# Level_Shift_Breakout.net
KiCad netlist of a schematic drawn in EAGLE
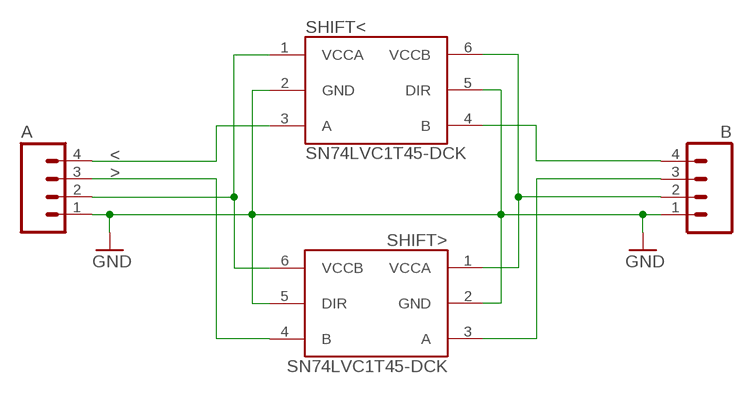
[diagram p0: schematic, sheet 1]

(export (version "E")
  (design (tool "Eeschema 10.0.6"))
  (components
    (comp (ref "A")
      (value "M04PTH")
      (footprint "eagle-import:1X04")
      (libsource (lib "eagle-import") (part "M04PTH"))
    )
    (comp (ref "B")
      (value "M04PTH")
      (footprint "eagle-import:1X04")
      (libsource (lib "eagle-import") (part "M04PTH"))
    )
    (comp (ref "SHIFT<")
      (value "SN74LVC1T45-DCK")
      (footprint "eagle-import:SC70")
      (libsource (lib "eagle-import") (part "SN74LVC1T45-DCK"))
    )
    (comp (ref "SHIFT>")
      (value "SN74LVC1T45-DCK")
      (footprint "eagle-import:SC70")
      (libsource (lib "eagle-import") (part "SN74LVC1T45-DCK"))
    )
  )
  (nets
    (net (code "1") (name "/<") (class "Default")
      (node (ref "A") (pin "4") (pinfunction "4_4") (pintype "passive"))
      (node (ref "SHIFT<") (pin "3") (pinfunction "A_3") (pintype "bidirectional"))
    )
    (net (code "2") (name "/>") (class "Default")
      (node (ref "A") (pin "3") (pinfunction "3_3") (pintype "passive"))
      (node (ref "SHIFT>") (pin "4") (pinfunction "B_4") (pintype "bidirectional"))
    )
    (net (code "3") (name "GND") (class "Default")
      (node (ref "A") (pin "1") (pinfunction "1_1") (pintype "passive"))
      (node (ref "B") (pin "1") (pinfunction "1_1") (pintype "passive"))
      (node (ref "SHIFT<") (pin "2") (pinfunction "GND_2") (pintype "bidirectional"))
      (node (ref "SHIFT<") (pin "5") (pinfunction "DIR_5") (pintype "bidirectional"))
      (node (ref "SHIFT>") (pin "2") (pinfunction "GND_2") (pintype "bidirectional"))
      (node (ref "SHIFT>") (pin "5") (pinfunction "DIR_5") (pintype "bidirectional"))
    )
    (net (code "4") (name "Net-(SHIFT<-B)") (class "Default")
      (node (ref "B") (pin "4") (pinfunction "4_4") (pintype "passive"))
      (node (ref "SHIFT<") (pin "4") (pinfunction "B_4") (pintype "bidirectional"))
    )
    (net (code "5") (name "Net-(SHIFT<-VCCA)") (class "Default")
      (node (ref "A") (pin "2") (pinfunction "2_2") (pintype "passive"))
      (node (ref "SHIFT<") (pin "1") (pinfunction "VCCA_1") (pintype "bidirectional"))
      (node (ref "SHIFT>") (pin "6") (pinfunction "VCCB_6") (pintype "bidirectional"))
    )
    (net (code "6") (name "Net-(SHIFT<-VCCB)") (class "Default")
      (node (ref "B") (pin "2") (pinfunction "2_2") (pintype "passive"))
      (node (ref "SHIFT<") (pin "6") (pinfunction "VCCB_6") (pintype "bidirectional"))
      (node (ref "SHIFT>") (pin "1") (pinfunction "VCCA_1") (pintype "bidirectional"))
    )
    (net (code "7") (name "Net-(SHIFT>-A)") (class "Default")
      (node (ref "B") (pin "3") (pinfunction "3_3") (pintype "passive"))
      (node (ref "SHIFT>") (pin "3") (pinfunction "A_3") (pintype "bidirectional"))
    )
  )
)
